# Sensor.net
KiCad netlist of a schematic drawn in Altium Designer
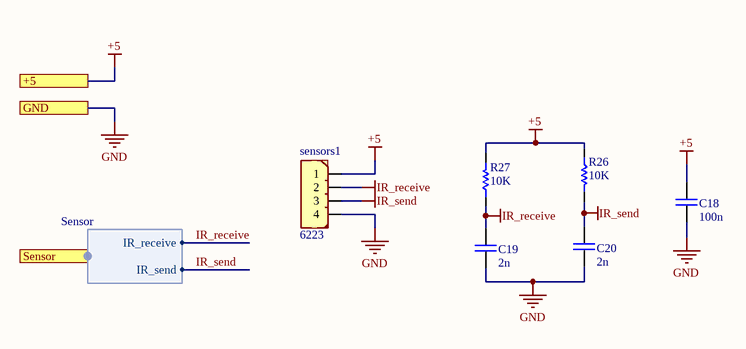
[diagram p0: Sensor.SchDoc]

(export (version "E")
  (design (tool "Eeschema 10.0.6"))
  (components
    (comp (ref "C18")
      (value "100n")
      (footprint "CAP 1206/3216")
      (description "Bipolar ceramic capacitor SMD")
      (fields (field (name "VALIDATION") "Valid"))
      (libsource (lib "aKaReZa") (part "Cap_Multi_SMD_100nF_1206"))
    )
    (comp (ref "C19")
      (value "2n")
      (footprint "CAP 1206/3216")
      (description "Bipolar ceramic capacitor SMD")
      (fields (field (name "VALIDATION") "Valid"))
      (libsource (lib "aKaReZa") (part "Cap_Multi_SMD_100nF_1206"))
    )
    (comp (ref "C20")
      (value "2n")
      (footprint "CAP 1206/3216")
      (description "Bipolar ceramic capacitor SMD")
      (fields (field (name "VALIDATION") "Valid"))
      (libsource (lib "aKaReZa") (part "Cap_Multi_SMD_100nF_1206"))
    )
    (comp (ref "R26")
      (value "10K")
      (footprint "RES 1206 (3216X08L)")
      (description "Resistor")
      (fields (field (name "VALIDATION") "Valid"))
      (libsource (lib "aKaReZa") (part "Res_SMD_1206"))
    )
    (comp (ref "R27")
      (value "10K")
      (footprint "RES 1206 (3216X08L)")
      (description "Resistor")
      (fields (field (name "VALIDATION") "Valid"))
      (libsource (lib "aKaReZa") (part "Res_SMD_1206"))
    )
    (comp (ref "sensors1")
      (value "4'Pin")
      (footprint "645004114822")
      (description "4'Pin Power Connector")
      (fields (field (name "INFLOW") "6223") (field (name "VALIDATION") "Valid"))
      (libsource (lib "aKaReZa") (part "Con_Power_4_PC_V"))
    )
  )
  (nets
    (net (code "2") (name "+5") (class "Default")
      (node (ref "C18") (pin "1") (pinfunction "1_1") (pintype "passive"))
      (node (ref "R26") (pin "1") (pinfunction "1_1") (pintype "passive"))
      (node (ref "R27") (pin "2") (pinfunction "2_2") (pintype "passive"))
      (node (ref "sensors1") (pin "1") (pinfunction "1_1") (pintype "passive"))
    )
    (net (code "4") (name "GND") (class "Default")
      (node (ref "C18") (pin "2") (pinfunction "2_2") (pintype "passive"))
      (node (ref "C19") (pin "2") (pinfunction "2_2") (pintype "passive"))
      (node (ref "C20") (pin "2") (pinfunction "2_2") (pintype "passive"))
      (node (ref "sensors1") (pin "4") (pinfunction "4_4") (pintype "passive"))
    )
    (net (code "5") (name "IR_receive") (class "Default")
      (node (ref "C19") (pin "1") (pinfunction "1_1") (pintype "passive"))
      (node (ref "R27") (pin "1") (pinfunction "1_1") (pintype "passive"))
      (node (ref "sensors1") (pin "2") (pinfunction "2_2") (pintype "passive"))
    )
    (net (code "6") (name "IR_send") (class "Default")
      (node (ref "C20") (pin "1") (pinfunction "1_1") (pintype "passive"))
      (node (ref "R26") (pin "2") (pinfunction "2_2") (pintype "passive"))
      (node (ref "sensors1") (pin "3") (pinfunction "3_3") (pintype "passive"))
    )
  )
)
